# 7BotSCH.net
KiCad netlist of a schematic drawn in Altium Designer
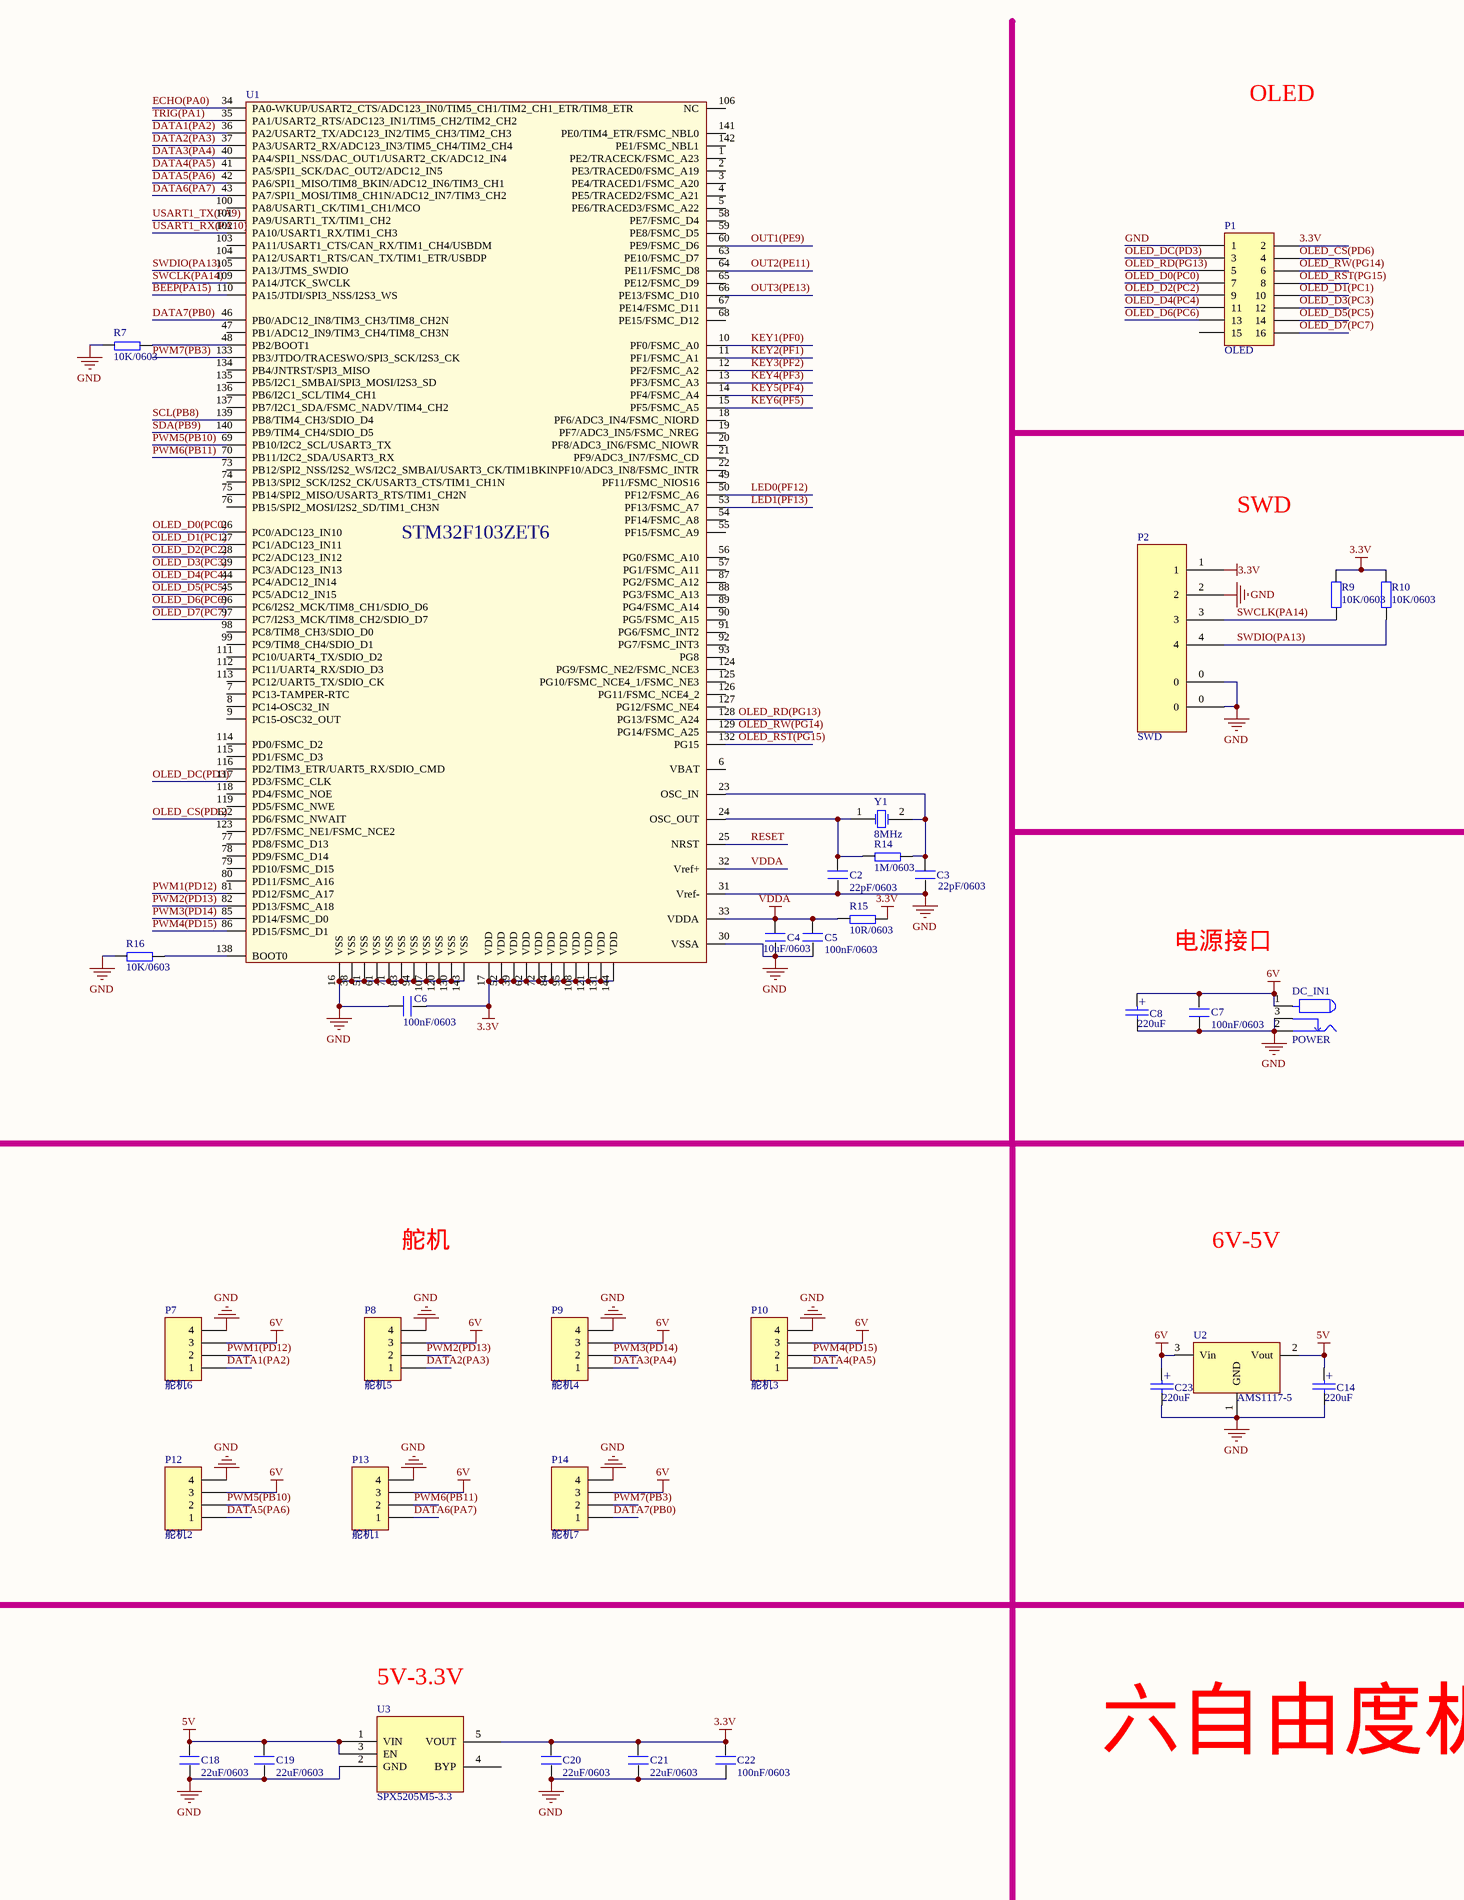
[diagram p0: 7BotSCH.SchDoc, left]
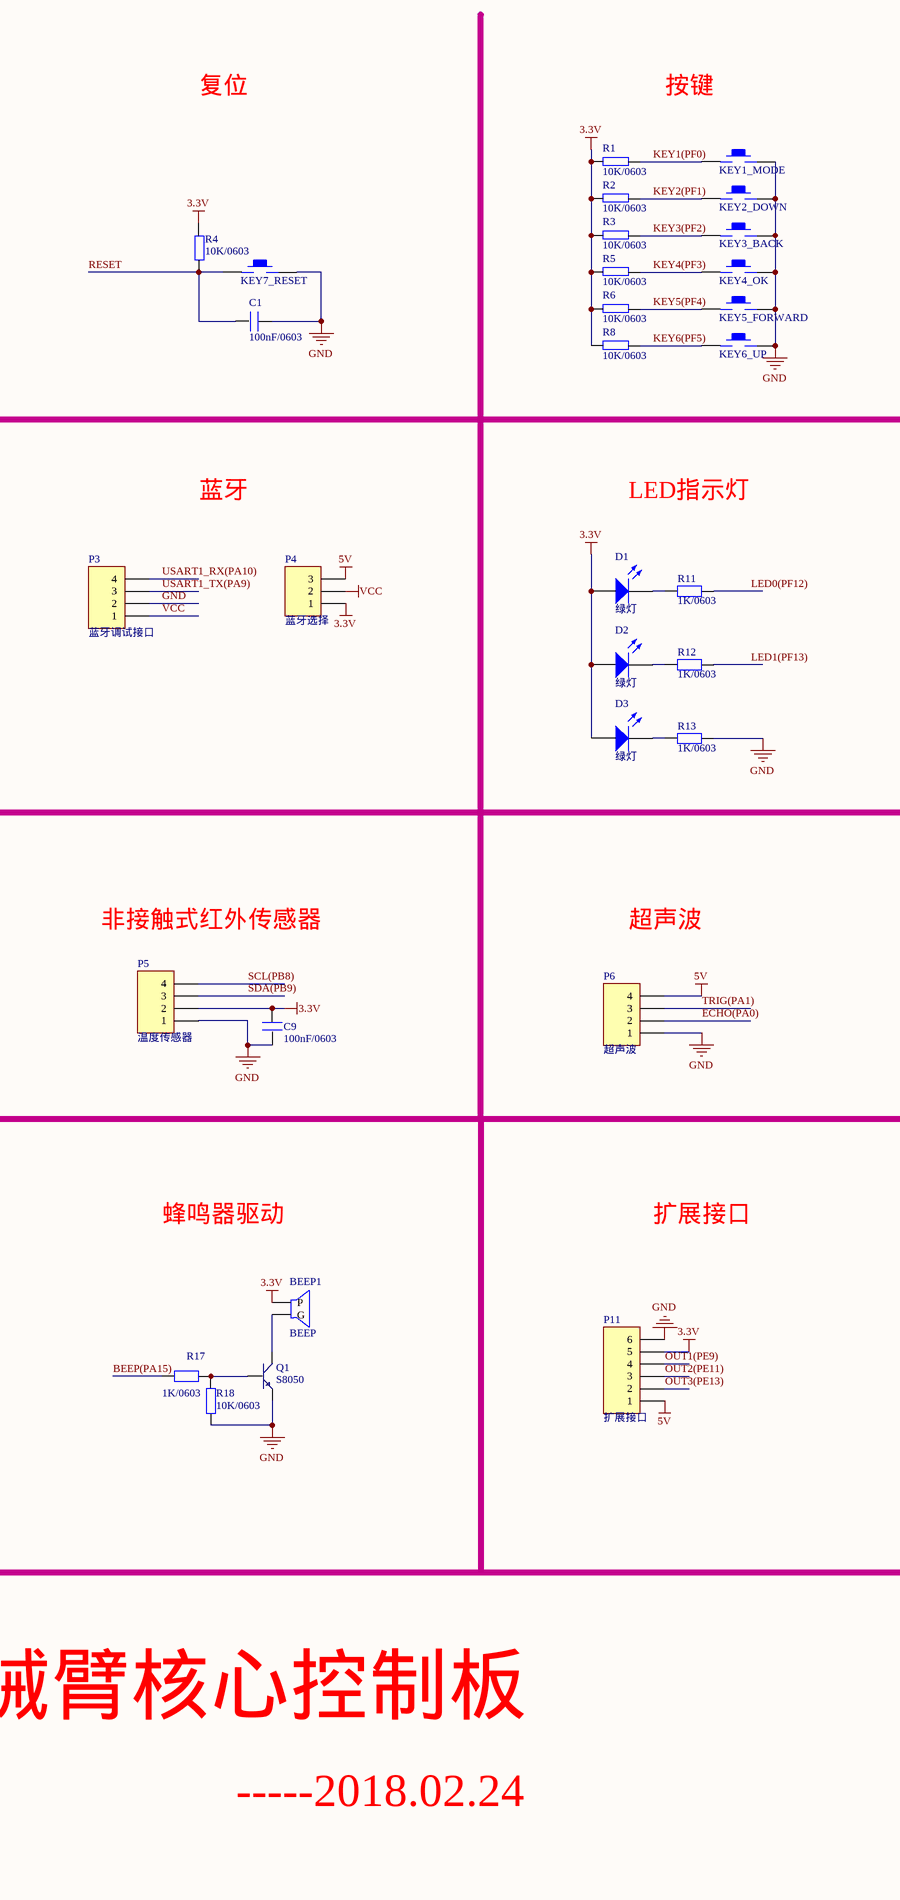
[diagram p1: 7BotSCH.SchDoc, right]

(export (version "E")
  (design (tool "Eeschema 10.0.6"))
  (components
    (comp (ref "BEEP1")
      (value "BEEP")
      (footprint "BELL-5")
      (libsource (lib "Explorer STM32F407封装库") (part "BEEP"))
    )
    (comp (ref "C1")
      (value "100nF/0603")
      (footprint "0603-1")
      (libsource (lib "Integrated_Library1") (part "C_3"))
    )
    (comp (ref "C2") (value "22pF/0603") (footprint "0603-1") (libsource (lib "EliteSTM32封装库") (part "C")))
    (comp (ref "C3") (value "22pF/0603") (footprint "0603-1") (libsource (lib "EliteSTM32封装库") (part "C")))
    (comp (ref "C4") (value "10uF/0603") (footprint "0603-1") (libsource (lib "EliteSTM32封装库") (part "C_2")))
    (comp (ref "C5") (value "100nF/0603") (footprint "0603-1") (libsource (lib "EliteSTM32封装库") (part "C")))
    (comp (ref "C6")
      (value "100nF/0603")
      (footprint "0603-1")
      (libsource (lib "Integrated_Library1") (part "C_3"))
    )
    (comp (ref "C7")
      (value "100nF/0603")
      (footprint "0603-1")
      (libsource (lib "Integrated_Library1") (part "C_3"))
    )
    (comp (ref "C8") (value "220uF") (footprint "1210") (libsource (lib "常用元件库") (part "Cap Pol")))
    (comp (ref "C9")
      (value "100nF/0603")
      (footprint "0603-1")
      (libsource (lib "Integrated_Library1") (part "C_3"))
    )
    (comp (ref "C14") (value "220uF") (footprint "1210") (libsource (lib "常用元件库") (part "Cap Pol")))
    (comp (ref "C18")
      (value "22uF/0603")
      (footprint "0603-1")
      (libsource (lib "Integrated_Library1") (part "C_3"))
    )
    (comp (ref "C19")
      (value "22uF/0603")
      (footprint "0603-1")
      (libsource (lib "Integrated_Library1") (part "C_3"))
    )
    (comp (ref "C20")
      (value "22uF/0603")
      (footprint "0603-1")
      (libsource (lib "Integrated_Library1") (part "C_3"))
    )
    (comp (ref "C21")
      (value "22uF/0603")
      (footprint "0603-1")
      (libsource (lib "Integrated_Library1") (part "C_3"))
    )
    (comp (ref "C22")
      (value "100nF/0603")
      (footprint "0603-1")
      (libsource (lib "Integrated_Library1") (part "C_3"))
    )
    (comp (ref "C23") (value "220uF") (footprint "1210") (libsource (lib "常用元件库") (part "Cap Pol")))
    (comp (ref "D1")
      (value "绿灯")
      (footprint "0603-1")
      (description "发光二极管")
      (fields (field (name "PUBLISHER") "Altium Limited"))
      (libsource (lib "fszhang") (part "LED0"))
    )
    (comp (ref "D2")
      (value "绿灯")
      (footprint "0603-1")
      (description "发光二极管")
      (fields (field (name "PUBLISHER") "Altium Limited"))
      (libsource (lib "fszhang") (part "LED0"))
    )
    (comp (ref "D3")
      (value "绿灯")
      (footprint "0603-1")
      (description "发光二极管")
      (fields (field (name "PUBLISHER") "Altium Limited"))
      (libsource (lib "fszhang") (part "LED0"))
    )
    (comp (ref "DC_IN1")
      (value "POWER")
      (footprint "DC10B")
      (libsource (lib "Explorer STM32F407封装库") (part "POW"))
    )
    (comp (ref "KEY1_MODE") (value "KEY_M") (footprint "KEY_M") (libsource (lib "底板封装库") (part "KEY_M")))
    (comp (ref "KEY2_DOWN") (value "KEY_M") (footprint "KEY_M") (libsource (lib "底板封装库") (part "KEY_M")))
    (comp (ref "KEY3_BACK") (value "KEY_M") (footprint "KEY_M") (libsource (lib "底板封装库") (part "KEY_M")))
    (comp (ref "KEY4_OK") (value "KEY_M") (footprint "KEY_M") (libsource (lib "底板封装库") (part "KEY_M")))
    (comp (ref "KEY5_FORWARD") (value "KEY_M") (footprint "KEY_M") (libsource (lib "底板封装库") (part "KEY_M")))
    (comp (ref "KEY6_UP") (value "KEY_M") (footprint "KEY_M") (libsource (lib "底板封装库") (part "KEY_M")))
    (comp (ref "KEY7_RESET") (value "KEY_M") (footprint "KEY_M") (libsource (lib "底板封装库") (part "KEY_M")))
    (comp (ref "P1")
      (value "OLED")
      (footprint "HDR2X8")
      (description "Header, 8-Pin, Dual row")
      (fields (field (name "PUBLISHER") "Altium Limited"))
      (libsource (lib "Miscellaneous Connectors") (part "Header 8X2"))
    )
    (comp (ref "P2") (value "SWD") (footprint "MOLEX4脚") (libsource (lib "Schlib1") (part "MOLEX4")))
    (comp (ref "P3")
      (value "蓝牙调试接口")
      (footprint "HDR1X4")
      (description "Header, 4-Pin")
      (fields (field (name "PUBLISHER") "Altium Limited"))
      (libsource (lib "九轴数据采集") (part "Header 4"))
    )
    (comp (ref "P4")
      (value "蓝牙选择")
      (footprint "HDR1X3")
      (description "Header, 3-Pin")
      (fields (field (name "PUBLISHER") "Altium Limited"))
      (libsource (lib "Miscellaneous Connectors") (part "Header 3"))
    )
    (comp (ref "P5")
      (value "温度传感器")
      (footprint "HDR1X4")
      (description "Header, 4-Pin")
      (fields (field (name "PUBLISHER") "Altium Limited"))
      (libsource (lib "Miscellaneous Connectors") (part "Header 4"))
    )
    (comp (ref "P6")
      (value "超声波")
      (footprint "HDR1X4")
      (description "Header, 4-Pin")
      (fields (field (name "PUBLISHER") "Altium Limited"))
      (libsource (lib "Miscellaneous Connectors") (part "Header 4"))
    )
    (comp (ref "P7")
      (value "舵机6")
      (footprint "HDR1X4")
      (description "Header, 4-Pin")
      (fields (field (name "PUBLISHER") "Altium Limited"))
      (libsource (lib "九轴数据采集") (part "Header 4"))
    )
    (comp (ref "P8")
      (value "舵机5")
      (footprint "HDR1X4")
      (description "Header, 4-Pin")
      (fields (field (name "PUBLISHER") "Altium Limited"))
      (libsource (lib "九轴数据采集") (part "Header 4"))
    )
    (comp (ref "P9")
      (value "舵机4")
      (footprint "HDR1X4")
      (description "Header, 4-Pin")
      (fields (field (name "PUBLISHER") "Altium Limited"))
      (libsource (lib "九轴数据采集") (part "Header 4"))
    )
    (comp (ref "P10")
      (value "舵机3")
      (footprint "HDR1X4")
      (description "Header, 4-Pin")
      (fields (field (name "PUBLISHER") "Altium Limited"))
      (libsource (lib "九轴数据采集") (part "Header 4"))
    )
    (comp (ref "P11")
      (value "扩展接口")
      (footprint "HDR1X6")
      (description "Header, 6-Pin")
      (fields (field (name "PUBLISHER") "Altium Limited"))
      (libsource (lib "Miscellaneous Connectors") (part "Header 6"))
    )
    (comp (ref "P12")
      (value "舵机2")
      (footprint "HDR1X4")
      (description "Header, 4-Pin")
      (fields (field (name "PUBLISHER") "Altium Limited"))
      (libsource (lib "九轴数据采集") (part "Header 4"))
    )
    (comp (ref "P13")
      (value "舵机1")
      (footprint "HDR1X4")
      (description "Header, 4-Pin")
      (fields (field (name "PUBLISHER") "Altium Limited"))
      (libsource (lib "九轴数据采集") (part "Header 4"))
    )
    (comp (ref "P14")
      (value "舵机7")
      (footprint "HDR1X4")
      (description "Header, 4-Pin")
      (fields (field (name "PUBLISHER") "Altium Limited"))
      (libsource (lib "九轴数据采集") (part "Header 4"))
    )
    (comp (ref "Q1")
      (value "S8050")
      (footprint "SOT-23R")
      (description "8050/BCW846/BCW847")
      (libsource (lib "Explorer STM32F407封装库") (part "NPN"))
    )
    (comp (ref "R1") (value "10K/0603") (footprint "0603-1") (libsource (lib "EliteSTM32封装库") (part "R_1")))
    (comp (ref "R2") (value "10K/0603") (footprint "0603-1") (libsource (lib "EliteSTM32封装库") (part "R_1")))
    (comp (ref "R3") (value "10K/0603") (footprint "0603-1") (libsource (lib "EliteSTM32封装库") (part "R_1")))
    (comp (ref "R4") (value "10K/0603") (footprint "0603-1") (libsource (lib "EliteSTM32封装库") (part "R_1")))
    (comp (ref "R5") (value "10K/0603") (footprint "0603-1") (libsource (lib "EliteSTM32封装库") (part "R_1")))
    (comp (ref "R6") (value "10K/0603") (footprint "0603-1") (libsource (lib "EliteSTM32封装库") (part "R_1")))
    (comp (ref "R7") (value "10K/0603") (footprint "0603-1") (libsource (lib "EliteSTM32封装库") (part "R_1")))
    (comp (ref "R8") (value "10K/0603") (footprint "0603-1") (libsource (lib "EliteSTM32封装库") (part "R_1")))
    (comp (ref "R9")
      (value "10K/0603")
      (footprint "0603-1")
      (description "贴片电阻")
      (fields (field (name "PUBLISHER") "Altium Limited"))
      (libsource (lib "") (part "Res1_3"))
    )
    (comp (ref "R10")
      (value "10K/0603")
      (footprint "0603-1")
      (description "贴片电阻")
      (fields (field (name "PUBLISHER") "Altium Limited"))
      (libsource (lib "") (part "Res1_3"))
    )
    (comp (ref "R11")
      (value "1K/0603")
      (footprint "0603-1")
      (description "贴片电阻")
      (fields (field (name "PUBLISHER") "Altium Limited"))
      (libsource (lib "fszhang") (part "Res1"))
    )
    (comp (ref "R12")
      (value "1K/0603")
      (footprint "0603-1")
      (description "贴片电阻")
      (fields (field (name "PUBLISHER") "Altium Limited"))
      (libsource (lib "fszhang") (part "Res1"))
    )
    (comp (ref "R13")
      (value "1K/0603")
      (footprint "0603-1")
      (description "贴片电阻")
      (fields (field (name "PUBLISHER") "Altium Limited"))
      (libsource (lib "fszhang") (part "Res1"))
    )
    (comp (ref "R14") (value "1M/0603") (footprint "0603-1") (libsource (lib "EliteSTM32封装库") (part "R_1")))
    (comp (ref "R15") (value "10R/0603") (footprint "0603-1") (libsource (lib "EliteSTM32封装库") (part "R_1")))
    (comp (ref "R16") (value "10K/0603") (footprint "0603-1") (libsource (lib "EliteSTM32封装库") (part "R_1")))
    (comp (ref "R17")
      (value "1K/0603")
      (footprint "0603-1")
      (description "贴片电阻")
      (fields (field (name "Comment") "Res1") (field (name "PUBLISHER") "Altium Limited"))
      (libsource (lib "") (part "Res1_2"))
    )
    (comp (ref "R18")
      (value "10K/0603")
      (footprint "0603-1")
      (description "贴片电阻")
      (fields (field (name "Comment") "Res1") (field (name "PUBLISHER") "Altium Limited"))
      (libsource (lib "") (part "Res1_1"))
    )
    (comp (ref "U1")
      (value "STM32F103ZET6")
      (footprint "LQFP144")
      (libsource (lib "EliteSTM32封装库") (part "STM32F103ZET6"))
    )
    (comp (ref "U2") (value "AMS1117-5") (footprint "SOT-223L") (libsource (lib "IC") (part "1117")))
    (comp (ref "U3")
      (value "SPX5205M5-3.3")
      (footprint "SOT23-5")
      (libsource (lib "Schlib1") (part "SPX5205M5-3.3V"))
    )
    (comp (ref "Y1")
      (value "8MHz")
      (footprint "25M两脚无源晶振5032")
      (description "Crystal Oscillator")
      (fields (field (name "PUBLISHER") "Altium Limited"))
      (libsource (lib "EliteSTM32封装库") (part "XTAL"))
    )
  )
  (nets
    (net (code "1") (name "/BEEP(PA15)") (class "Default")
      (node (ref "R17") (pin "1") (pinfunction "1_1") (pintype "passive"))
      (node (ref "U1") (pin "110") (pinfunction "PA15/JTDI/SPI3_NSS/I2S3_WS_110") (pintype "passive"))
    )
    (net (code "2") (name "/DATA1(PA2)") (class "Default")
      (node (ref "P7") (pin "1") (pinfunction "1_1") (pintype "passive"))
      (node (ref "U1") (pin "36") (pinfunction "PA2/USART2_TX/ADC123_IN2/TIM5_CH3/TIM2_CH3_36") (pintype "passive"))
    )
    (net (code "3") (name "/DATA2(PA3)") (class "Default")
      (node (ref "P8") (pin "1") (pinfunction "1_1") (pintype "passive"))
      (node (ref "U1") (pin "37") (pinfunction "PA3/USART2_RX/ADC123_IN3/TIM5_CH4/TIM2_CH4_37") (pintype "passive"))
    )
    (net (code "4") (name "/DATA3(PA4)") (class "Default")
      (node (ref "P9") (pin "1") (pinfunction "1_1") (pintype "passive"))
      (node (ref "U1") (pin "40") (pinfunction "PA4/SPI1_NSS/DAC_OUT1/USART2_CK/ADC12_IN4_40") (pintype "passive"))
    )
    (net (code "5") (name "/DATA4(PA5)") (class "Default")
      (node (ref "P10") (pin "1") (pinfunction "1_1") (pintype "passive"))
      (node (ref "U1") (pin "41") (pinfunction "PA5/SPI1_SCK/DAC_OUT2/ADC12_IN5_41") (pintype "passive"))
    )
    (net (code "6") (name "/DATA5(PA6)") (class "Default")
      (node (ref "P12") (pin "1") (pinfunction "1_1") (pintype "passive"))
      (node (ref "U1") (pin "42") (pinfunction "PA6/SPI1_MISO/TIM8_BKIN/ADC12_IN6/TIM3_CH1_42") (pintype "passive"))
    )
    (net (code "7") (name "/DATA6(PA7)") (class "Default")
      (node (ref "P13") (pin "1") (pinfunction "1_1") (pintype "passive"))
      (node (ref "U1") (pin "43") (pinfunction "PA7/SPI1_MOSI/TIM8_CH1N/ADC12_IN7/TIM3_CH2_43") (pintype "passive"))
    )
    (net (code "8") (name "/DATA7(PB0)") (class "Default")
      (node (ref "P14") (pin "1") (pinfunction "1_1") (pintype "passive"))
      (node (ref "U1") (pin "46") (pinfunction "PB0/ADC12_IN8/TIM3_CH3/TIM8_CH2N_46") (pintype "passive"))
    )
    (net (code "9") (name "/ECHO(PA0)") (class "Default")
      (node (ref "P6") (pin "2") (pinfunction "2_2") (pintype "passive"))
      (node (ref "U1") (pin "34") (pinfunction "PA0-WKUP/USART2_CTS/ADC123_IN0/TIM5_CH1/TIM2_CH1_ETR/TIM8_ETR_34") (pintype "passive"))
    )
    (net (code "10") (name "/KEY1(PF0)") (class "Default")
      (node (ref "KEY1_MODE") (pin "1") (pinfunction "1_1") (pintype "passive"))
      (node (ref "R1") (pin "1") (pintype "passive"))
      (node (ref "U1") (pin "10") (pinfunction "PF0/FSMC_A0_10") (pintype "passive"))
    )
    (net (code "11") (name "/KEY2(PF1)") (class "Default")
      (node (ref "KEY2_DOWN") (pin "1") (pinfunction "1_1") (pintype "passive"))
      (node (ref "R2") (pin "1") (pintype "passive"))
      (node (ref "U1") (pin "11") (pinfunction "PF1/FSMC_A1_11") (pintype "passive"))
    )
    (net (code "12") (name "/KEY3(PF2)") (class "Default")
      (node (ref "KEY3_BACK") (pin "1") (pinfunction "1_1") (pintype "passive"))
      (node (ref "R3") (pin "1") (pintype "passive"))
      (node (ref "U1") (pin "12") (pinfunction "PF2/FSMC_A2_12") (pintype "passive"))
    )
    (net (code "13") (name "/KEY4(PF3)") (class "Default")
      (node (ref "KEY4_OK") (pin "1") (pinfunction "1_1") (pintype "passive"))
      (node (ref "R5") (pin "1") (pintype "passive"))
      (node (ref "U1") (pin "13") (pinfunction "PF3/FSMC_A3_13") (pintype "passive"))
    )
    (net (code "14") (name "/KEY5(PF4)") (class "Default")
      (node (ref "KEY5_FORWARD") (pin "1") (pinfunction "1_1") (pintype "passive"))
      (node (ref "R6") (pin "1") (pintype "passive"))
      (node (ref "U1") (pin "14") (pinfunction "PF4/FSMC_A4_14") (pintype "passive"))
    )
    (net (code "15") (name "/KEY6(PF5)") (class "Default")
      (node (ref "KEY6_UP") (pin "1") (pinfunction "1_1") (pintype "passive"))
      (node (ref "R8") (pin "1") (pintype "passive"))
      (node (ref "U1") (pin "15") (pinfunction "PF5/FSMC_A5_15") (pintype "passive"))
    )
    (net (code "16") (name "/LED0(PF12)") (class "Default")
      (node (ref "R11") (pin "1") (pinfunction "1_1") (pintype "passive"))
      (node (ref "U1") (pin "50") (pinfunction "PF12/FSMC_A6_50") (pintype "passive"))
    )
    (net (code "17") (name "/LED1(PF13)") (class "Default")
      (node (ref "R12") (pin "1") (pinfunction "1_1") (pintype "passive"))
      (node (ref "U1") (pin "53") (pinfunction "PF13/FSMC_A7_53") (pintype "passive"))
    )
    (net (code "18") (name "/OLED_CS(PD6)") (class "Default")
      (node (ref "P1") (pin "4") (pinfunction "4_4") (pintype "passive"))
      (node (ref "U1") (pin "122") (pinfunction "PD6/FSMC_NWAIT_122") (pintype "passive"))
    )
    (net (code "19") (name "/OLED_D0(PC0)") (class "Default")
      (node (ref "P1") (pin "7") (pinfunction "7_7") (pintype "passive"))
      (node (ref "U1") (pin "26") (pinfunction "PC0/ADC123_IN10_26") (pintype "passive"))
    )
    (net (code "20") (name "/OLED_D1(PC1)") (class "Default")
      (node (ref "P1") (pin "10") (pinfunction "10_10") (pintype "passive"))
      (node (ref "U1") (pin "27") (pinfunction "PC1/ADC123_IN11_27") (pintype "passive"))
    )
    (net (code "21") (name "/OLED_D2(PC2)") (class "Default")
      (node (ref "P1") (pin "9") (pinfunction "9_9") (pintype "passive"))
      (node (ref "U1") (pin "28") (pinfunction "PC2/ADC123_IN12_28") (pintype "passive"))
    )
    (net (code "22") (name "/OLED_D3(PC3)") (class "Default")
      (node (ref "P1") (pin "12") (pinfunction "12_12") (pintype "passive"))
      (node (ref "U1") (pin "29") (pinfunction "PC3/ADC123_IN13_29") (pintype "passive"))
    )
    (net (code "23") (name "/OLED_D4(PC4)") (class "Default")
      (node (ref "P1") (pin "11") (pinfunction "11_11") (pintype "passive"))
      (node (ref "U1") (pin "44") (pinfunction "PC4/ADC12_IN14_44") (pintype "passive"))
    )
    (net (code "24") (name "/OLED_D5(PC5)") (class "Default")
      (node (ref "P1") (pin "14") (pinfunction "14_14") (pintype "passive"))
      (node (ref "U1") (pin "45") (pinfunction "PC5/ADC12_IN15_45") (pintype "passive"))
    )
    (net (code "25") (name "/OLED_D6(PC6)") (class "Default")
      (node (ref "P1") (pin "13") (pinfunction "13_13") (pintype "passive"))
      (node (ref "U1") (pin "96") (pinfunction "PC6/I2S2_MCK/TIM8_CH1/SDIO_D6_96") (pintype "passive"))
    )
    (net (code "26") (name "/OLED_D7(PC7)") (class "Default")
      (node (ref "P1") (pin "16") (pinfunction "16_16") (pintype "passive"))
      (node (ref "U1") (pin "97") (pinfunction "PC7/I2S3_MCK/TIM8_CH2/SDIO_D7_97") (pintype "passive"))
    )
    (net (code "27") (name "/OLED_DC(PD3)") (class "Default")
      (node (ref "P1") (pin "3") (pinfunction "3_3") (pintype "passive"))
      (node (ref "U1") (pin "117") (pinfunction "PD3/FSMC_CLK_117") (pintype "passive"))
    )
    (net (code "28") (name "/OLED_RD(PG13)") (class "Default")
      (node (ref "P1") (pin "5") (pinfunction "5_5") (pintype "passive"))
      (node (ref "U1") (pin "128") (pinfunction "PG13/FSMC_A24_128") (pintype "passive"))
    )
    (net (code "29") (name "/OLED_RST(PG15)") (class "Default")
      (node (ref "P1") (pin "8") (pinfunction "8_8") (pintype "passive"))
      (node (ref "U1") (pin "132") (pinfunction "PG15_132") (pintype "passive"))
    )
    (net (code "30") (name "/OLED_RW(PG14)") (class "Default")
      (node (ref "P1") (pin "6") (pinfunction "6_6") (pintype "passive"))
      (node (ref "U1") (pin "129") (pinfunction "PG14/FSMC_A25_129") (pintype "passive"))
    )
    (net (code "31") (name "/OUT1(PE9)") (class "Default")
      (node (ref "P11") (pin "4") (pinfunction "4_4") (pintype "passive"))
      (node (ref "U1") (pin "60") (pinfunction "PE9/FSMC_D6_60") (pintype "passive"))
    )
    (net (code "32") (name "/OUT2(PE11)") (class "Default")
      (node (ref "P11") (pin "3") (pinfunction "3_3") (pintype "passive"))
      (node (ref "U1") (pin "64") (pinfunction "PE11/FSMC_D8_64") (pintype "passive"))
    )
    (net (code "33") (name "/OUT3(PE13)") (class "Default")
      (node (ref "P11") (pin "2") (pinfunction "2_2") (pintype "passive"))
      (node (ref "U1") (pin "66") (pinfunction "PE13/FSMC_D10_66") (pintype "passive"))
    )
    (net (code "34") (name "/PWM1(PD12)") (class "Default")
      (node (ref "P7") (pin "2") (pinfunction "2_2") (pintype "passive"))
      (node (ref "U1") (pin "81") (pinfunction "PD12/FSMC_A17_81") (pintype "passive"))
    )
    (net (code "35") (name "/PWM2(PD13)") (class "Default")
      (node (ref "P8") (pin "2") (pinfunction "2_2") (pintype "passive"))
      (node (ref "U1") (pin "82") (pinfunction "PD13/FSMC_A18_82") (pintype "passive"))
    )
    (net (code "36") (name "/PWM3(PD14)") (class "Default")
      (node (ref "P9") (pin "2") (pinfunction "2_2") (pintype "passive"))
      (node (ref "U1") (pin "85") (pinfunction "PD14/FSMC_D0_85") (pintype "passive"))
    )
    (net (code "37") (name "/PWM4(PD15)") (class "Default")
      (node (ref "P10") (pin "2") (pinfunction "2_2") (pintype "passive"))
      (node (ref "U1") (pin "86") (pinfunction "PD15/FSMC_D1_86") (pintype "passive"))
    )
    (net (code "38") (name "/PWM5(PB10)") (class "Default")
      (node (ref "P12") (pin "2") (pinfunction "2_2") (pintype "passive"))
      (node (ref "U1") (pin "69") (pinfunction "PB10/I2C2_SCL/USART3_TX_69") (pintype "passive"))
    )
    (net (code "39") (name "/PWM6(PB11)") (class "Default")
      (node (ref "P13") (pin "2") (pinfunction "2_2") (pintype "passive"))
      (node (ref "U1") (pin "70") (pinfunction "PB11/I2C2_SDA/USART3_RX_70") (pintype "passive"))
    )
    (net (code "40") (name "/PWM7(PB3)") (class "Default")
      (node (ref "P14") (pin "2") (pinfunction "2_2") (pintype "passive"))
      (node (ref "U1") (pin "133") (pinfunction "PB3/JTDO/TRACESWO/SPI3_SCK/I2S3_CK_133") (pintype "passive"))
    )
    (net (code "41") (name "/RESET") (class "Default")
      (node (ref "C1") (pin "2") (pintype "passive"))
      (node (ref "KEY7_RESET") (pin "1") (pinfunction "1_1") (pintype "passive"))
      (node (ref "R4") (pin "1") (pintype "passive"))
      (node (ref "U1") (pin "25") (pinfunction "NRST_25") (pintype "passive"))
    )
    (net (code "42") (name "/SCL(PB8)") (class "Default")
      (node (ref "P5") (pin "4") (pinfunction "4_4") (pintype "passive"))
      (node (ref "U1") (pin "139") (pinfunction "PB8/TIM4_CH3/SDIO_D4_139") (pintype "passive"))
    )
    (net (code "43") (name "/SDA(PB9)") (class "Default")
      (node (ref "P5") (pin "3") (pinfunction "3_3") (pintype "passive"))
      (node (ref "U1") (pin "140") (pinfunction "PB9/TIM4_CH4/SDIO_D5_140") (pintype "passive"))
    )
    (net (code "44") (name "/SWCLK(PA14)") (class "Default")
      (node (ref "P2") (pin "3") (pinfunction "3_3") (pintype "passive"))
      (node (ref "R9") (pin "2") (pinfunction "2_2") (pintype "passive"))
      (node (ref "U1") (pin "109") (pinfunction "PA14/JTCK_SWCLK_109") (pintype "passive"))
    )
    (net (code "45") (name "/SWDIO(PA13)") (class "Default")
      (node (ref "P2") (pin "4") (pinfunction "4_4") (pintype "passive"))
      (node (ref "R10") (pin "2") (pinfunction "2_2") (pintype "passive"))
      (node (ref "U1") (pin "105") (pinfunction "PA13/JTMS_SWDIO_105") (pintype "passive"))
    )
    (net (code "46") (name "/TRIG(PA1)") (class "Default")
      (node (ref "P6") (pin "3") (pinfunction "3_3") (pintype "passive"))
      (node (ref "U1") (pin "35") (pinfunction "PA1/USART2_RTS/ADC123_IN1/TIM5_CH2/TIM2_CH2_35") (pintype "passive"))
    )
    (net (code "47") (name "/USART1_RX(PA10)") (class "Default")
      (node (ref "P3") (pin "4") (pinfunction "4_4") (pintype "passive"))
      (node (ref "U1") (pin "102") (pinfunction "PA10/USART1_RX/TIM1_CH3_102") (pintype "passive"))
    )
    (net (code "48") (name "/USART1_TX(PA9)") (class "Default")
      (node (ref "P3") (pin "3") (pinfunction "3_3") (pintype "passive"))
      (node (ref "U1") (pin "101") (pinfunction "PA9/USART1_TX/TIM1_CH2_101") (pintype "passive"))
    )
    (net (code "49") (name "3.3V") (class "Default")
      (node (ref "BEEP1") (pin "1") (pinfunction "P_1") (pintype "passive"))
      (node (ref "C20") (pin "2") (pintype "passive"))
      (node (ref "C21") (pin "2") (pintype "passive"))
      (node (ref "C22") (pin "2") (pintype "passive"))
      (node (ref "C6") (pin "2") (pintype "passive"))
      (node (ref "C9") (pin "2") (pintype "passive"))
      (node (ref "D1") (pin "1") (pinfunction "A_1") (pintype "passive"))
      (node (ref "D2") (pin "1") (pinfunction "A_1") (pintype "passive"))
      (node (ref "D3") (pin "1") (pinfunction "A_1") (pintype "passive"))
      (node (ref "P1") (pin "2") (pinfunction "2_2") (pintype "passive"))
      (node (ref "P11") (pin "5") (pinfunction "5_5") (pintype "passive"))
      (node (ref "P2") (pin "1") (pinfunction "1_1") (pintype "passive"))
      (node (ref "P4") (pin "1") (pinfunction "1_1") (pintype "passive"))
      (node (ref "P5") (pin "2") (pinfunction "2_2") (pintype "passive"))
      (node (ref "R1") (pin "2") (pintype "passive"))
      (node (ref "R10") (pin "1") (pinfunction "1_1") (pintype "passive"))
      (node (ref "R15") (pin "2") (pintype "passive"))
      (node (ref "R2") (pin "2") (pintype "passive"))
      (node (ref "R3") (pin "2") (pintype "passive"))
      (node (ref "R4") (pin "2") (pintype "passive"))
      (node (ref "R5") (pin "2") (pintype "passive"))
      (node (ref "R6") (pin "2") (pintype "passive"))
      (node (ref "R8") (pin "2") (pintype "passive"))
      (node (ref "R9") (pin "1") (pinfunction "1_1") (pintype "passive"))
      (node (ref "U1") (pin "108") (pinfunction "VDD_108") (pintype "passive"))
      (node (ref "U1") (pin "121") (pinfunction "VDD_121") (pintype "passive"))
      (node (ref "U1") (pin "131") (pinfunction "VDD_131") (pintype "passive"))
      (node (ref "U1") (pin "144") (pinfunction "VDD_144") (pintype "passive"))
      (node (ref "U1") (pin "17") (pinfunction "VDD_17") (pintype "passive"))
      (node (ref "U1") (pin "39") (pinfunction "VDD_39") (pintype "passive"))
      (node (ref "U1") (pin "52") (pinfunction "VDD_52") (pintype "passive"))
      (node (ref "U1") (pin "62") (pinfunction "VDD_62") (pintype "passive"))
      (node (ref "U1") (pin "72") (pinfunction "VDD_72") (pintype "passive"))
      (node (ref "U1") (pin "84") (pinfunction "VDD_84") (pintype "passive"))
      (node (ref "U1") (pin "95") (pinfunction "VDD_95") (pintype "passive"))
      (node (ref "U3") (pin "5") (pinfunction "VOUT_5") (pintype "passive"))
    )
    (net (code "50") (name "5V") (class "Default")
      (node (ref "C14") (pin "1") (pinfunction "1_1") (pintype "passive"))
      (node (ref "C18") (pin "2") (pintype "passive"))
      (node (ref "C19") (pin "2") (pintype "passive"))
      (node (ref "P11") (pin "1") (pinfunction "1_1") (pintype "passive"))
      (node (ref "P4") (pin "3") (pinfunction "3_3") (pintype "passive"))
      (node (ref "P6") (pin "4") (pinfunction "4_4") (pintype "passive"))
      (node (ref "U2") (pin "2") (pinfunction "Vout_2") (pintype "passive"))
      (node (ref "U3") (pin "1") (pinfunction "VIN_1") (pintype "passive"))
      (node (ref "U3") (pin "3") (pinfunction "EN_3") (pintype "passive"))
    )
    (net (code "51") (name "6V") (class "Default")
      (node (ref "C23") (pin "1") (pinfunction "1_1") (pintype "passive"))
      (node (ref "C7") (pin "1") (pintype "passive"))
      (node (ref "C8") (pin "1") (pinfunction "1_1") (pintype "passive"))
      (node (ref "DC_IN1") (pin "1") (pintype "passive"))
      (node (ref "P10") (pin "3") (pinfunction "3_3") (pintype "passive"))
      (node (ref "P12") (pin "3") (pinfunction "3_3") (pintype "passive"))
      (node (ref "P13") (pin "3") (pinfunction "3_3") (pintype "passive"))
      (node (ref "P14") (pin "3") (pinfunction "3_3") (pintype "passive"))
      (node (ref "P7") (pin "3") (pinfunction "3_3") (pintype "passive"))
      (node (ref "P8") (pin "3") (pinfunction "3_3") (pintype "passive"))
      (node (ref "P9") (pin "3") (pinfunction "3_3") (pintype "passive"))
      (node (ref "U2") (pin "3") (pinfunction "Vin_3") (pintype "power_in"))
    )
    (net (code "52") (name "GND") (class "Default")
      (node (ref "C1") (pin "1") (pintype "passive"))
      (node (ref "C14") (pin "2") (pinfunction "2_2") (pintype "passive"))
      (node (ref "C18") (pin "1") (pintype "passive"))
      (node (ref "C19") (pin "1") (pintype "passive"))
      (node (ref "C2") (pin "1") (pintype "passive"))
      (node (ref "C20") (pin "1") (pintype "passive"))
      (node (ref "C21") (pin "1") (pintype "passive"))
      (node (ref "C22") (pin "1") (pintype "passive"))
      (node (ref "C23") (pin "2") (pinfunction "2_2") (pintype "passive"))
      (node (ref "C3") (pin "1") (pintype "passive"))
      (node (ref "C4") (pin "1") (pintype "passive"))
      (node (ref "C5") (pin "1") (pintype "passive"))
      (node (ref "C6") (pin "1") (pintype "passive"))
      (node (ref "C7") (pin "2") (pintype "passive"))
      (node (ref "C8") (pin "2") (pinfunction "2_2") (pintype "passive"))
      (node (ref "C9") (pin "1") (pintype "passive"))
      (node (ref "DC_IN1") (pin "2") (pintype "passive"))
      (node (ref "DC_IN1") (pin "3") (pintype "passive"))
      (node (ref "KEY1_MODE") (pin "2") (pinfunction "2_2") (pintype "passive"))
      (node (ref "KEY2_DOWN") (pin "2") (pinfunction "2_2") (pintype "passive"))
      (node (ref "KEY3_BACK") (pin "2") (pinfunction "2_2") (pintype "passive"))
      (node (ref "KEY4_OK") (pin "2") (pinfunction "2_2") (pintype "passive"))
      (node (ref "KEY5_FORWARD") (pin "2") (pinfunction "2_2") (pintype "passive"))
      (node (ref "KEY6_UP") (pin "2") (pinfunction "2_2") (pintype "passive"))
      (node (ref "KEY7_RESET") (pin "2") (pinfunction "2_2") (pintype "passive"))
      (node (ref "P1") (pin "1") (pinfunction "1_1") (pintype "passive"))
      (node (ref "P10") (pin "4") (pinfunction "4_4") (pintype "passive"))
      (node (ref "P11") (pin "6") (pinfunction "6_6") (pintype "passive"))
      (node (ref "P12") (pin "4") (pinfunction "4_4") (pintype "passive"))
      (node (ref "P13") (pin "4") (pinfunction "4_4") (pintype "passive"))
      (node (ref "P14") (pin "4") (pinfunction "4_4") (pintype "passive"))
      (node (ref "P2") (pin "0") (pinfunction "0_0") (pintype "passive"))
      (node (ref "P2") (pin "2") (pinfunction "2_2") (pintype "passive"))
      (node (ref "P3") (pin "2") (pinfunction "2_2") (pintype "passive"))
      (node (ref "P5") (pin "1") (pinfunction "1_1") (pintype "passive"))
      (node (ref "P6") (pin "1") (pinfunction "1_1") (pintype "passive"))
      (node (ref "P7") (pin "4") (pinfunction "4_4") (pintype "passive"))
      (node (ref "P8") (pin "4") (pinfunction "4_4") (pintype "passive"))
      (node (ref "P9") (pin "4") (pinfunction "4_4") (pintype "passive"))
      (node (ref "Q1") (pin "1") (pinfunction "E_1") (pintype "passive"))
      (node (ref "R13") (pin "1") (pinfunction "1_1") (pintype "passive"))
      (node (ref "R16") (pin "1") (pintype "passive"))
      (node (ref "R18") (pin "1") (pinfunction "1_1") (pintype "passive"))
      (node (ref "R7") (pin "1") (pintype "passive"))
      (node (ref "U1") (pin "107") (pinfunction "VSS_107") (pintype "passive"))
      (node (ref "U1") (pin "120") (pinfunction "VSS_120") (pintype "passive"))
      (node (ref "U1") (pin "130") (pinfunction "VSS_130") (pintype "passive"))
      (node (ref "U1") (pin "143") (pinfunction "VSS_143") (pintype "passive"))
      (node (ref "U1") (pin "16") (pinfunction "VSS_16") (pintype "passive"))
      (node (ref "U1") (pin "30") (pinfunction "VSSA_30") (pintype "passive"))
      (node (ref "U1") (pin "31") (pinfunction "Vref-_31") (pintype "passive"))
      (node (ref "U1") (pin "38") (pinfunction "VSS_38") (pintype "passive"))
      (node (ref "U1") (pin "51") (pinfunction "VSS_51") (pintype "passive"))
      (node (ref "U1") (pin "61") (pinfunction "VSS_61") (pintype "passive"))
      (node (ref "U1") (pin "71") (pinfunction "VSS_71") (pintype "passive"))
      (node (ref "U1") (pin "83") (pinfunction "VSS_83") (pintype "passive"))
      (node (ref "U1") (pin "94") (pinfunction "VSS_94") (pintype "passive"))
      (node (ref "U2") (pin "1") (pinfunction "GND_1") (pintype "power_in"))
      (node (ref "U3") (pin "2") (pinfunction "GND_2") (pintype "passive"))
    )
    (net (code "53") (name "Net-(BEEP1-G)") (class "Default")
      (node (ref "BEEP1") (pin "2") (pinfunction "G_2") (pintype "passive"))
      (node (ref "Q1") (pin "3") (pinfunction "C_3") (pintype "passive"))
    )
    (net (code "54") (name "Net-(D1-K)") (class "Default")
      (node (ref "D1") (pin "2") (pinfunction "K_2") (pintype "passive"))
      (node (ref "R11") (pin "2") (pinfunction "2_2") (pintype "passive"))
    )
    (net (code "55") (name "Net-(D2-K)") (class "Default")
      (node (ref "D2") (pin "2") (pinfunction "K_2") (pintype "passive"))
      (node (ref "R12") (pin "2") (pinfunction "2_2") (pintype "passive"))
    )
    (net (code "56") (name "Net-(D3-K)") (class "Default")
      (node (ref "D3") (pin "2") (pinfunction "K_2") (pintype "passive"))
      (node (ref "R13") (pin "2") (pinfunction "2_2") (pintype "passive"))
    )
    (net (code "57") (name "Net-(Q1-B)") (class "Default")
      (node (ref "Q1") (pin "2") (pinfunction "B_2") (pintype "passive"))
      (node (ref "R17") (pin "2") (pinfunction "2_2") (pintype "passive"))
      (node (ref "R18") (pin "2") (pinfunction "2_2") (pintype "passive"))
    )
    (net (code "58") (name "Net-(U1-BOOT0)") (class "Default")
      (node (ref "R16") (pin "2") (pintype "passive"))
      (node (ref "U1") (pin "138") (pinfunction "BOOT0_138") (pintype "passive"))
    )
    (net (code "59") (name "Net-(U1-OSC_IN)") (class "Default")
      (node (ref "C3") (pin "2") (pintype "passive"))
      (node (ref "R14") (pin "2") (pintype "passive"))
      (node (ref "U1") (pin "23") (pinfunction "OSC_IN_23") (pintype "passive"))
      (node (ref "Y1") (pin "2") (pinfunction "OSC2_2") (pintype "passive"))
    )
    (net (code "60") (name "Net-(U1-OSC_OUT)") (class "Default")
      (node (ref "C2") (pin "2") (pintype "passive"))
      (node (ref "R14") (pin "1") (pintype "passive"))
      (node (ref "U1") (pin "24") (pinfunction "OSC_OUT_24") (pintype "passive"))
      (node (ref "Y1") (pin "1") (pinfunction "OSC1_1") (pintype "passive"))
    )
    (net (code "61") (name "Net-(U1-PB2{slash}BOOT1)") (class "Default")
      (node (ref "R7") (pin "2") (pintype "passive"))
      (node (ref "U1") (pin "48") (pinfunction "PB2/BOOT1_48") (pintype "passive"))
    )
    (net (code "62") (name "VCC") (class "Default")
      (node (ref "P3") (pin "1") (pinfunction "1_1") (pintype "passive"))
      (node (ref "P4") (pin "2") (pinfunction "2_2") (pintype "passive"))
    )
    (net (code "63") (name "VDDA") (class "Default")
      (node (ref "C4") (pin "2") (pintype "passive"))
      (node (ref "C5") (pin "2") (pintype "passive"))
      (node (ref "R15") (pin "1") (pintype "passive"))
      (node (ref "U1") (pin "32") (pinfunction "Vref+_32") (pintype "passive"))
      (node (ref "U1") (pin "33") (pinfunction "VDDA_33") (pintype "passive"))
    )
    (net (code "64") (name "unconnected-(P1-Pad15)") (class "Default")
      (node (ref "P1") (pin "15") (pinfunction "15_15") (pintype "passive"))
    )
    (net (code "65") (name "unconnected-(U1-NC-Pad106)") (class "Default")
      (node (ref "U1") (pin "106") (pinfunction "NC_106") (pintype "passive"))
    )
    (net (code "66") (name "unconnected-(U1-PA8{slash}USART1_CK{slash}TIM1_CH1{slash}MCO-Pad100)") (class "Default")
      (node (ref "U1") (pin "100") (pinfunction "PA8/USART1_CK/TIM1_CH1/MCO_100") (pintype "passive"))
    )
    (net (code "67") (name "unconnected-(U1-PA11{slash}USART1_CTS{slash}CAN_RX{slash}TIM1_CH4{slash}USBDM-Pad103)") (class "Default")
      (node (ref "U1") (pin "103") (pinfunction "PA11/USART1_CTS/CAN_RX/TIM1_CH4/USBDM_103") (pintype "passive"))
    )
    (net (code "68") (name "unconnected-(U1-PA12{slash}USART1_RTS{slash}CAN_TX{slash}TIM1_ETR{slash}USBDP-Pad104)") (class "Default")
      (node (ref "U1") (pin "104") (pinfunction "PA12/USART1_RTS/CAN_TX/TIM1_ETR/USBDP_104") (pintype "passive"))
    )
    (net (code "69") (name "unconnected-(U1-PB1{slash}ADC12_IN9{slash}TIM3_CH4{slash}TIM8_CH3N-Pad47)") (class "Default")
      (node (ref "U1") (pin "47") (pinfunction "PB1/ADC12_IN9/TIM3_CH4/TIM8_CH3N_47") (pintype "passive"))
    )
    (net (code "70") (name "unconnected-(U1-PB4{slash}JNTRST{slash}SPI3_MISO-Pad134)") (class "Default")
      (node (ref "U1") (pin "134") (pinfunction "PB4/JNTRST/SPI3_MISO_134") (pintype "passive"))
    )
    (net (code "71") (name "unconnected-(U1-PB5{slash}I2C1_SMBAI{slash}SPI3_MOSI{slash}I2S3_SD-Pad135)") (class "Default")
      (node (ref "U1") (pin "135") (pinfunction "PB5/I2C1_SMBAI/SPI3_MOSI/I2S3_SD_135") (pintype "passive"))
    )
    (net (code "72") (name "unconnected-(U1-PB6{slash}I2C1_SCL{slash}TIM4_CH1-Pad136)") (class "Default")
      (node (ref "U1") (pin "136") (pinfunction "PB6/I2C1_SCL/TIM4_CH1_136") (pintype "passive"))
    )
    (net (code "73") (name "unconnected-(U1-PB7{slash}I2C1_SDA{slash}FSMC_NADV{slash}TIM4_CH2-Pad137)") (class "Default")
      (node (ref "U1") (pin "137") (pinfunction "PB7/I2C1_SDA/FSMC_NADV/TIM4_CH2_137") (pintype "passive"))
    )
    (net (code "74") (name "unconnected-(U1-PB12{slash}SPI2_NSS{slash}I2S2_WS{slash}I2C2_SMBAI{slash}USART3_CK{slash}TIM1BKIN-Pad73)") (class "Default")
      (node (ref "U1") (pin "73") (pinfunction "PB12/SPI2_NSS/I2S2_WS/I2C2_SMBAI/USART3_CK/TIM1BKIN_73") (pintype "passive"))
    )
    (net (code "75") (name "unconnected-(U1-PB13{slash}SPI2_SCK{slash}I2S2_CK{slash}USART3_CTS{slash}TIM1_CH1N-Pad74)") (class "Default")
      (node (ref "U1") (pin "74") (pinfunction "PB13/SPI2_SCK/I2S2_CK/USART3_CTS/TIM1_CH1N_74") (pintype "passive"))
    )
    (net (code "76") (name "unconnected-(U1-PB14{slash}SPI2_MISO{slash}USART3_RTS{slash}TIM1_CH2N-Pad75)") (class "Default")
      (node (ref "U1") (pin "75") (pinfunction "PB14/SPI2_MISO/USART3_RTS/TIM1_CH2N_75") (pintype "passive"))
    )
    (net (code "77") (name "unconnected-(U1-PB15{slash}SPI2_MOSI{slash}I2S2_SD{slash}TIM1_CH3N-Pad76)") (class "Default")
      (node (ref "U1") (pin "76") (pinfunction "PB15/SPI2_MOSI/I2S2_SD/TIM1_CH3N_76") (pintype "passive"))
    )
    (net (code "78") (name "unconnected-(U1-PC8{slash}TIM8_CH3{slash}SDIO_D0-Pad98)") (class "Default")
      (node (ref "U1") (pin "98") (pinfunction "PC8/TIM8_CH3/SDIO_D0_98") (pintype "passive"))
    )
    (net (code "79") (name "unconnected-(U1-PC9{slash}TIM8_CH4{slash}SDIO_D1-Pad99)") (class "Default")
      (node (ref "U1") (pin "99") (pinfunction "PC9/TIM8_CH4/SDIO_D1_99") (pintype "passive"))
    )
    (net (code "80") (name "unconnected-(U1-PC10{slash}UART4_TX{slash}SDIO_D2-Pad111)") (class "Default")
      (node (ref "U1") (pin "111") (pinfunction "PC10/UART4_TX/SDIO_D2_111") (pintype "passive"))
    )
    (net (code "81") (name "unconnected-(U1-PC11{slash}UART4_RX{slash}SDIO_D3-Pad112)") (class "Default")
      (node (ref "U1") (pin "112") (pinfunction "PC11/UART4_RX/SDIO_D3_112") (pintype "passive"))
    )
    (net (code "82") (name "unconnected-(U1-PC12{slash}UART5_TX{slash}SDIO_CK-Pad113)") (class "Default")
      (node (ref "U1") (pin "113") (pinfunction "PC12/UART5_TX/SDIO_CK_113") (pintype "passive"))
    )
    (net (code "83") (name "unconnected-(U1-PC13-TAMPER-RTC-Pad7)") (class "Default")
      (node (ref "U1") (pin "7") (pinfunction "PC13-TAMPER-RTC_7") (pintype "passive"))
    )
    (net (code "84") (name "unconnected-(U1-PC14-OSC32_IN-Pad8)") (class "Default")
      (node (ref "U1") (pin "8") (pinfunction "PC14-OSC32_IN_8") (pintype "passive"))
    )
    (net (code "85") (name "unconnected-(U1-PC15-OSC32_OUT-Pad9)") (class "Default")
      (node (ref "U1") (pin "9") (pinfunction "PC15-OSC32_OUT_9") (pintype "passive"))
    )
    (net (code "86") (name "unconnected-(U1-PD0{slash}FSMC_D2-Pad114)") (class "Default")
      (node (ref "U1") (pin "114") (pinfunction "PD0/FSMC_D2_114") (pintype "passive"))
    )
    (net (code "87") (name "unconnected-(U1-PD1{slash}FSMC_D3-Pad115)") (class "Default")
      (node (ref "U1") (pin "115") (pinfunction "PD1/FSMC_D3_115") (pintype "passive"))
    )
    (net (code "88") (name "unconnected-(U1-PD2{slash}TIM3_ETR{slash}UART5_RX{slash}SDIO_CMD-Pad116)") (class "Default")
      (node (ref "U1") (pin "116") (pinfunction "PD2/TIM3_ETR/UART5_RX/SDIO_CMD_116") (pintype "passive"))
    )
    (net (code "89") (name "unconnected-(U1-PD4{slash}FSMC_NOE-Pad118)") (class "Default")
      (node (ref "U1") (pin "118") (pinfunction "PD4/FSMC_NOE_118") (pintype "passive"))
    )
    (net (code "90") (name "unconnected-(U1-PD5{slash}FSMC_NWE-Pad119)") (class "Default")
      (node (ref "U1") (pin "119") (pinfunction "PD5/FSMC_NWE_119") (pintype "passive"))
    )
    (net (code "91") (name "unconnected-(U1-PD7{slash}FSMC_NE1{slash}FSMC_NCE2-Pad123)") (class "Default")
      (node (ref "U1") (pin "123") (pinfunction "PD7/FSMC_NE1/FSMC_NCE2_123") (pintype "passive"))
    )
    (net (code "92") (name "unconnected-(U1-PD8{slash}FSMC_D13-Pad77)") (class "Default")
      (node (ref "U1") (pin "77") (pinfunction "PD8/FSMC_D13_77") (pintype "passive"))
    )
    (net (code "93") (name "unconnected-(U1-PD9{slash}FSMC_D14-Pad78)") (class "Default")
      (node (ref "U1") (pin "78") (pinfunction "PD9/FSMC_D14_78") (pintype "passive"))
    )
    (net (code "94") (name "unconnected-(U1-PD10{slash}FSMC_D15-Pad79)") (class "Default")
      (node (ref "U1") (pin "79") (pinfunction "PD10/FSMC_D15_79") (pintype "passive"))
    )
    (net (code "95") (name "unconnected-(U1-PD11{slash}FSMC_A16-Pad80)") (class "Default")
      (node (ref "U1") (pin "80") (pinfunction "PD11/FSMC_A16_80") (pintype "passive"))
    )
    (net (code "96") (name "unconnected-(U1-PE0{slash}TIM4_ETR{slash}FSMC_NBL0-Pad141)") (class "Default")
      (node (ref "U1") (pin "141") (pinfunction "PE0/TIM4_ETR/FSMC_NBL0_141") (pintype "passive"))
    )
    (net (code "97") (name "unconnected-(U1-PE1{slash}FSMC_NBL1-Pad142)") (class "Default")
      (node (ref "U1") (pin "142") (pinfunction "PE1/FSMC_NBL1_142") (pintype "passive"))
    )
    (net (code "98") (name "unconnected-(U1-PE2{slash}TRACECK{slash}FSMC_A23-Pad1)") (class "Default")
      (node (ref "U1") (pin "1") (pinfunction "PE2/TRACECK/FSMC_A23_1") (pintype "passive"))
    )
    (net (code "99") (name "unconnected-(U1-PE3{slash}TRACED0{slash}FSMC_A19-Pad2)") (class "Default")
      (node (ref "U1") (pin "2") (pinfunction "PE3/TRACED0/FSMC_A19_2") (pintype "passive"))
    )
    (net (code "100") (name "unconnected-(U1-PE4{slash}TRACED1{slash}FSMC_A20-Pad3)") (class "Default")
      (node (ref "U1") (pin "3") (pinfunction "PE4/TRACED1/FSMC_A20_3") (pintype "passive"))
    )
    (net (code "101") (name "unconnected-(U1-PE5{slash}TRACED2{slash}FSMC_A21-Pad4)") (class "Default")
      (node (ref "U1") (pin "4") (pinfunction "PE5/TRACED2/FSMC_A21_4") (pintype "passive"))
    )
    (net (code "102") (name "unconnected-(U1-PE6{slash}TRACED3{slash}FSMC_A22-Pad5)") (class "Default")
      (node (ref "U1") (pin "5") (pinfunction "PE6/TRACED3/FSMC_A22_5") (pintype "passive"))
    )
    (net (code "103") (name "unconnected-(U1-PE7{slash}FSMC_D4-Pad58)") (class "Default")
      (node (ref "U1") (pin "58") (pinfunction "PE7/FSMC_D4_58") (pintype "passive"))
    )
    (net (code "104") (name "unconnected-(U1-PE8{slash}FSMC_D5-Pad59)") (class "Default")
      (node (ref "U1") (pin "59") (pinfunction "PE8/FSMC_D5_59") (pintype "passive"))
    )
    (net (code "105") (name "unconnected-(U1-PE10{slash}FSMC_D7-Pad63)") (class "Default")
      (node (ref "U1") (pin "63") (pinfunction "PE10/FSMC_D7_63") (pintype "passive"))
    )
    (net (code "106") (name "unconnected-(U1-PE12{slash}FSMC_D9-Pad65)") (class "Default")
      (node (ref "U1") (pin "65") (pinfunction "PE12/FSMC_D9_65") (pintype "passive"))
    )
    (net (code "107") (name "unconnected-(U1-PE14{slash}FSMC_D11-Pad67)") (class "Default")
      (node (ref "U1") (pin "67") (pinfunction "PE14/FSMC_D11_67") (pintype "passive"))
    )
    (net (code "108") (name "unconnected-(U1-PE15{slash}FSMC_D12-Pad68)") (class "Default")
      (node (ref "U1") (pin "68") (pinfunction "PE15/FSMC_D12_68") (pintype "passive"))
    )
    (net (code "109") (name "unconnected-(U1-PF6{slash}ADC3_IN4{slash}FSMC_NIORD-Pad18)") (class "Default")
      (node (ref "U1") (pin "18") (pinfunction "PF6/ADC3_IN4/FSMC_NIORD_18") (pintype "passive"))
    )
    (net (code "110") (name "unconnected-(U1-PF7{slash}ADC3_IN5{slash}FSMC_NREG-Pad19)") (class "Default")
      (node (ref "U1") (pin "19") (pinfunction "PF7/ADC3_IN5/FSMC_NREG_19") (pintype "passive"))
    )
    (net (code "111") (name "unconnected-(U1-PF8{slash}ADC3_IN6{slash}FSMC_NIOWR-Pad20)") (class "Default")
      (node (ref "U1") (pin "20") (pinfunction "PF8/ADC3_IN6/FSMC_NIOWR_20") (pintype "passive"))
    )
    (net (code "112") (name "unconnected-(U1-PF9{slash}ADC3_IN7{slash}FSMC_CD-Pad21)") (class "Default")
      (node (ref "U1") (pin "21") (pinfunction "PF9/ADC3_IN7/FSMC_CD_21") (pintype "passive"))
    )
    (net (code "113") (name "unconnected-(U1-PF10{slash}ADC3_IN8{slash}FSMC_INTR-Pad22)") (class "Default")
      (node (ref "U1") (pin "22") (pinfunction "PF10/ADC3_IN8/FSMC_INTR_22") (pintype "passive"))
    )
    (net (code "114") (name "unconnected-(U1-PF11{slash}FSMC_NIOS16-Pad49)") (class "Default")
      (node (ref "U1") (pin "49") (pinfunction "PF11/FSMC_NIOS16_49") (pintype "passive"))
    )
    (net (code "115") (name "unconnected-(U1-PF14{slash}FSMC_A8-Pad54)") (class "Default")
      (node (ref "U1") (pin "54") (pinfunction "PF14/FSMC_A8_54") (pintype "passive"))
    )
    (net (code "116") (name "unconnected-(U1-PF15{slash}FSMC_A9-Pad55)") (class "Default")
      (node (ref "U1") (pin "55") (pinfunction "PF15/FSMC_A9_55") (pintype "passive"))
    )
    (net (code "117") (name "unconnected-(U1-PG0{slash}FSMC_A10-Pad56)") (class "Default")
      (node (ref "U1") (pin "56") (pinfunction "PG0/FSMC_A10_56") (pintype "passive"))
    )
    (net (code "118") (name "unconnected-(U1-PG1{slash}FSMC_A11-Pad57)") (class "Default")
      (node (ref "U1") (pin "57") (pinfunction "PG1/FSMC_A11_57") (pintype "passive"))
    )
    (net (code "119") (name "unconnected-(U1-PG2{slash}FSMC_A12-Pad87)") (class "Default")
      (node (ref "U1") (pin "87") (pinfunction "PG2/FSMC_A12_87") (pintype "passive"))
    )
    (net (code "120") (name "unconnected-(U1-PG3{slash}FSMC_A13-Pad88)") (class "Default")
      (node (ref "U1") (pin "88") (pinfunction "PG3/FSMC_A13_88") (pintype "passive"))
    )
    (net (code "121") (name "unconnected-(U1-PG4{slash}FSMC_A14-Pad89)") (class "Default")
      (node (ref "U1") (pin "89") (pinfunction "PG4/FSMC_A14_89") (pintype "passive"))
    )
    (net (code "122") (name "unconnected-(U1-PG5{slash}FSMC_A15-Pad90)") (class "Default")
      (node (ref "U1") (pin "90") (pinfunction "PG5/FSMC_A15_90") (pintype "passive"))
    )
    (net (code "123") (name "unconnected-(U1-PG6{slash}FSMC_INT2-Pad91)") (class "Default")
      (node (ref "U1") (pin "91") (pinfunction "PG6/FSMC_INT2_91") (pintype "passive"))
    )
    (net (code "124") (name "unconnected-(U1-PG7{slash}FSMC_INT3-Pad92)") (class "Default")
      (node (ref "U1") (pin "92") (pinfunction "PG7/FSMC_INT3_92") (pintype "passive"))
    )
    (net (code "125") (name "unconnected-(U1-PG8-Pad93)") (class "Default")
      (node (ref "U1") (pin "93") (pinfunction "PG8_93") (pintype "passive"))
    )
    (net (code "126") (name "unconnected-(U1-PG9{slash}FSMC_NE2{slash}FSMC_NCE3-Pad124)") (class "Default")
      (node (ref "U1") (pin "124") (pinfunction "PG9/FSMC_NE2/FSMC_NCE3_124") (pintype "passive"))
    )
    (net (code "127") (name "unconnected-(U1-PG10{slash}FSMC_NCE4_1{slash}FSMC_NE3-Pad125)") (class "Default")
      (node (ref "U1") (pin "125") (pinfunction "PG10/FSMC_NCE4_1/FSMC_NE3_125") (pintype "passive"))
    )
    (net (code "128") (name "unconnected-(U1-PG11{slash}FSMC_NCE4_2-Pad126)") (class "Default")
      (node (ref "U1") (pin "126") (pinfunction "PG11/FSMC_NCE4_2_126") (pintype "passive"))
    )
    (net (code "129") (name "unconnected-(U1-PG12{slash}FSMC_NE4-Pad127)") (class "Default")
      (node (ref "U1") (pin "127") (pinfunction "PG12/FSMC_NE4_127") (pintype "passive"))
    )
    (net (code "130") (name "unconnected-(U1-VBAT-Pad6)") (class "Default")
      (node (ref "U1") (pin "6") (pinfunction "VBAT_6") (pintype "passive"))
    )
    (net (code "131") (name "unconnected-(U3-BYP-Pad4)") (class "Default")
      (node (ref "U3") (pin "4") (pinfunction "BYP_4") (pintype "passive"))
    )
  )
)
